# BabyDriver.net
KiCad netlist of a schematic drawn in EAGLE
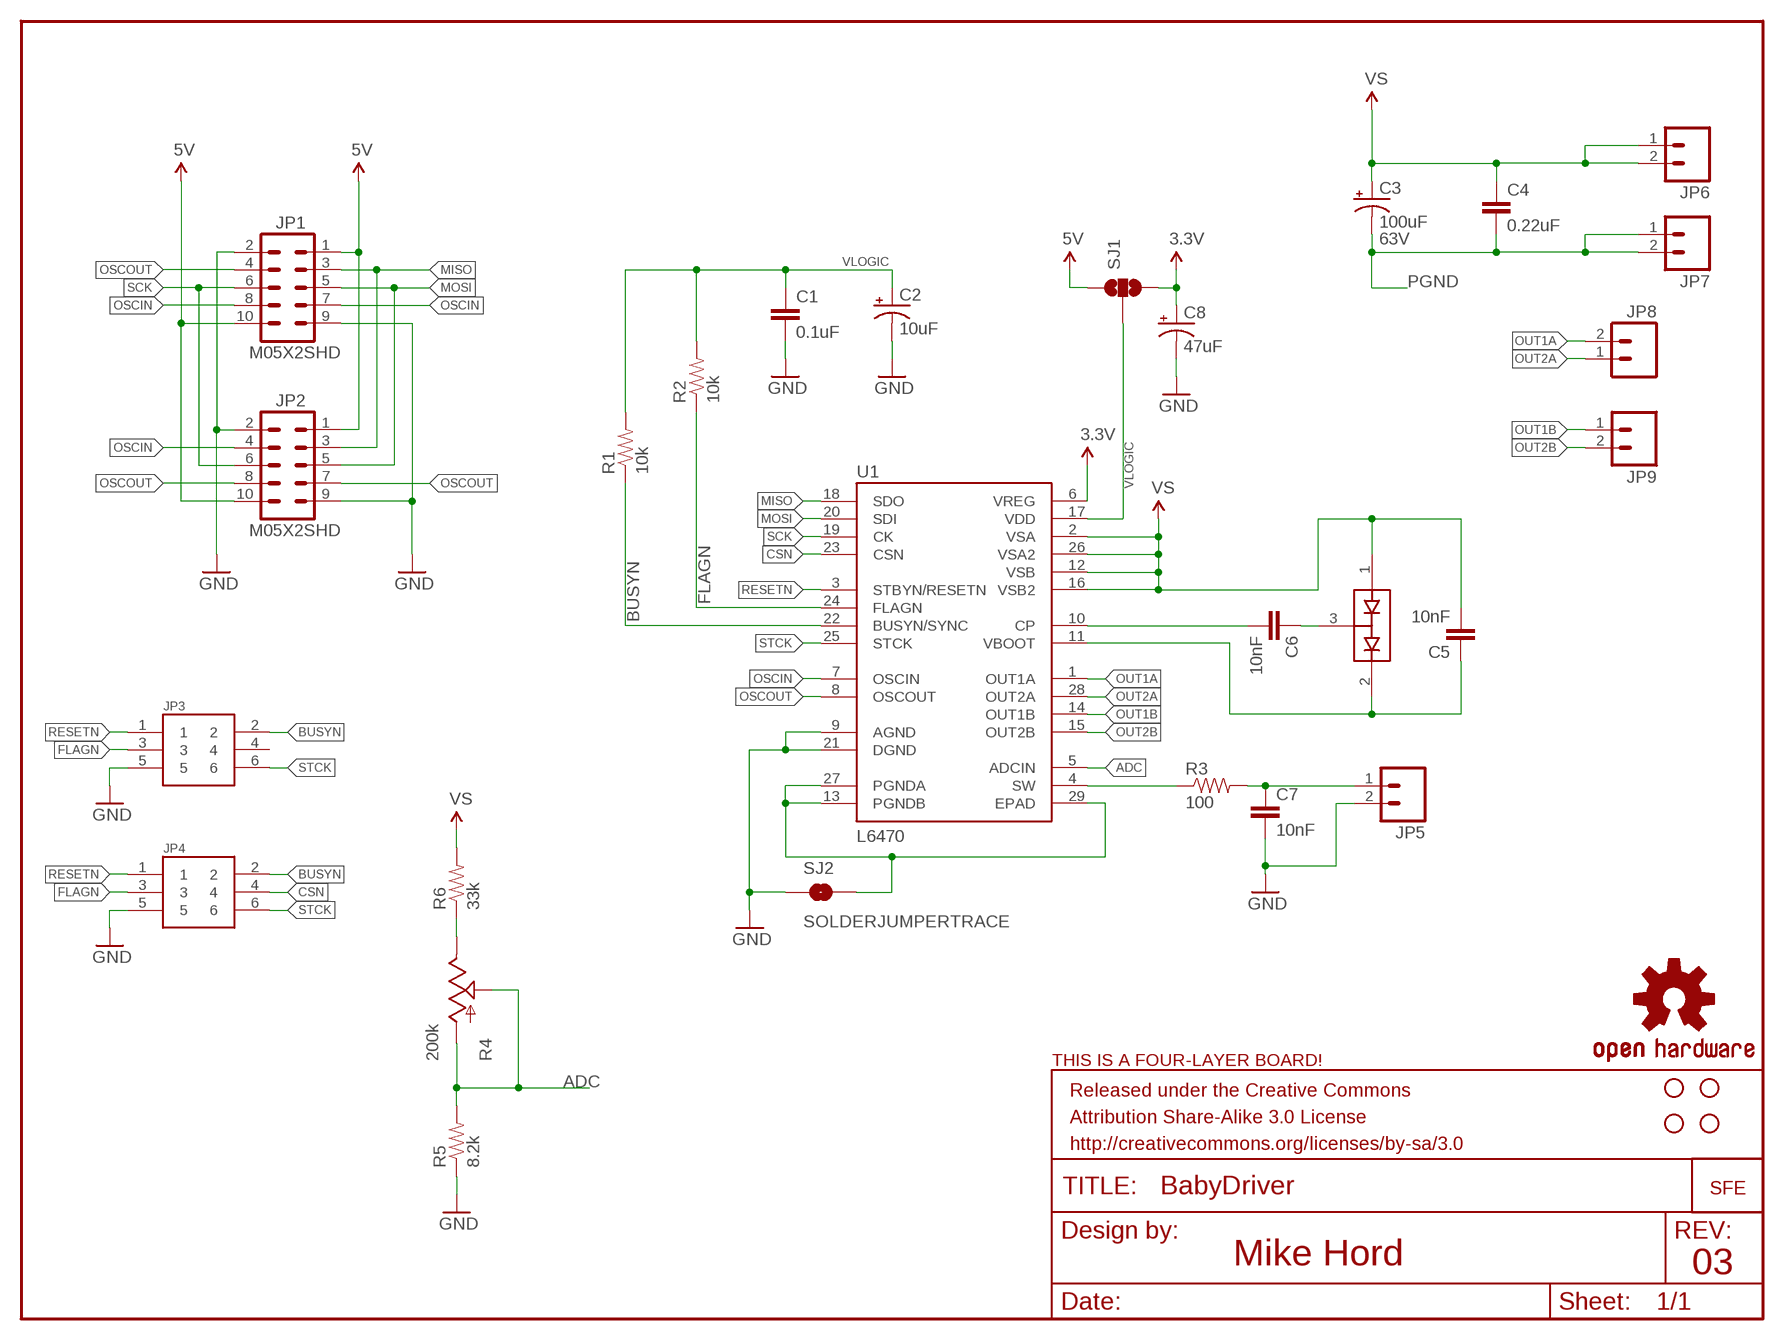
[diagram p0: schematic, sheet 1]

(export (version "E")
  (design (tool "Eeschema 10.0.6"))
  (components
    (comp (ref "C1")
      (value "0.1uF")
      (footprint "eagle-import:0402-CAP")
      (libsource (lib "eagle-import") (part ".1UF-CER"))
    )
    (comp (ref "C2")
      (value "10uF")
      (footprint "eagle-import:EIA3216")
      (libsource (lib "eagle-import") (part "10UF-TANT"))
    )
    (comp (ref "C3")
      (value "100uF")
      (footprint "eagle-import:PANASONIC_H13")
      (libsource (lib "eagle-import") (part "100UF-ELECT"))
    )
    (comp (ref "C4")
      (value "0.22uF")
      (footprint "eagle-import:0402-CAP")
      (libsource (lib "eagle-import") (part ".22UF-CER"))
    )
    (comp (ref "C5")
      (value "10nF")
      (footprint "eagle-import:0402-CAP")
      (libsource (lib "eagle-import") (part "10NF-CER"))
    )
    (comp (ref "C6")
      (value "10nF")
      (footprint "eagle-import:0402-CAP")
      (libsource (lib "eagle-import") (part "10NF-CER"))
    )
    (comp (ref "C7")
      (value "10nF")
      (footprint "eagle-import:0402-CAP")
      (libsource (lib "eagle-import") (part "10NF-CER"))
    )
    (comp (ref "C8")
      (value "47uF")
      (footprint "eagle-import:EIA3528")
      (libsource (lib "eagle-import") (part "47UF-TANT"))
    )
    (comp (ref "D1")
      (value "BAV99")
      (footprint "eagle-import:SOT23")
      (libsource (lib "eagle-import") (part "BAV99"))
    )
    (comp (ref "FRAME1")
      (value "FRAME-LETTER")
      (footprint "eagle-import:CREATIVE_COMMONS")
      (libsource (lib "eagle-import") (part "FRAME-LETTER"))
    )
    (comp (ref "JP1")
      (value "M05X2SHD")
      (footprint "eagle-import:2X5-SHROUDED")
      (libsource (lib "eagle-import") (part "M05X2SHD"))
    )
    (comp (ref "JP2")
      (value "M05X2SHD")
      (footprint "eagle-import:2X5-SHROUDED")
      (libsource (lib "eagle-import") (part "M05X2SHD"))
    )
    (comp (ref "JP3")
      (value "M03X2")
      (footprint "eagle-import:2X3-SHROUDED")
      (libsource (lib "eagle-import") (part "M03X2"))
    )
    (comp (ref "JP4")
      (value "M03X2")
      (footprint "eagle-import:2X3-SHROUDED")
      (libsource (lib "eagle-import") (part "M03X2"))
    )
    (comp (ref "JP5")
      (value "M023.5MM")
      (footprint "eagle-import:SCREWTERMINAL-3.5MM-2")
      (libsource (lib "eagle-import") (part "M023.5MM"))
    )
    (comp (ref "JP6")
      (value "M023.5MM")
      (footprint "eagle-import:SCREWTERMINAL-3.5MM-2")
      (libsource (lib "eagle-import") (part "M023.5MM"))
    )
    (comp (ref "JP7")
      (value "M023.5MM")
      (footprint "eagle-import:SCREWTERMINAL-3.5MM-2")
      (libsource (lib "eagle-import") (part "M023.5MM"))
    )
    (comp (ref "JP8")
      (value "M023.5MM")
      (footprint "eagle-import:SCREWTERMINAL-3.5MM-2")
      (libsource (lib "eagle-import") (part "M023.5MM"))
    )
    (comp (ref "JP9")
      (value "M023.5MM")
      (footprint "eagle-import:SCREWTERMINAL-3.5MM-2")
      (libsource (lib "eagle-import") (part "M023.5MM"))
    )
    (comp (ref "LOGO1")
      (value "OSHW-LOGOS")
      (footprint "eagle-import:OSHW-LOGO-S")
      (libsource (lib "eagle-import") (part "OSHW-LOGOS"))
    )
    (comp (ref "LOGO2")
      (value "LOGO-SFENEW")
      (footprint "eagle-import:SFE-NEW-WEBLOGO")
      (libsource (lib "eagle-import") (part "LOGO-SFENEW"))
    )
    (comp (ref "R1")
      (value "10k")
      (footprint "eagle-import:0402-RES")
      (libsource (lib "eagle-import") (part "10K-1%RES-00824"))
    )
    (comp (ref "R2")
      (value "10k")
      (footprint "eagle-import:0402-RES")
      (libsource (lib "eagle-import") (part "10K-1%RES-00824"))
    )
    (comp (ref "R3")
      (value "100")
      (footprint "eagle-import:0402-RES")
      (libsource (lib "eagle-import") (part "100-1%"))
    )
    (comp (ref "R4")
      (value "200k")
      (footprint "eagle-import:3362U")
      (libsource (lib "eagle-import") (part "POT100K_3362U"))
    )
    (comp (ref "R5")
      (value "8.2k")
      (footprint "eagle-import:0402-RES")
      (libsource (lib "eagle-import") (part "8.2K-5%"))
    )
    (comp (ref "R6")
      (value "33k")
      (footprint "eagle-import:0402-RES")
      (libsource (lib "eagle-import") (part "33K-1%"))
    )
    (comp (ref "SJ1")
      (value "SOLDERJUMPER_2WAYPASTE1&2")
      (footprint "eagle-import:SJ_3_PASTE1&2")
      (libsource (lib "eagle-import") (part "SOLDERJUMPER_2WAYPASTE1&2"))
    )
    (comp (ref "SJ2")
      (value "SOLDERJUMPERTRACE")
      (footprint "eagle-import:SJ_2S-TRACE")
      (libsource (lib "eagle-import") (part "SOLDERJUMPERTRACE"))
    )
    (comp (ref "STANDOFF1")
      (value "STAND-OFF")
      (footprint "eagle-import:STAND-OFF")
      (libsource (lib "eagle-import") (part "STAND-OFF"))
    )
    (comp (ref "STANDOFF2")
      (value "STAND-OFF")
      (footprint "eagle-import:STAND-OFF")
      (libsource (lib "eagle-import") (part "STAND-OFF"))
    )
    (comp (ref "STANDOFF3")
      (value "STAND-OFF")
      (footprint "eagle-import:STAND-OFF")
      (libsource (lib "eagle-import") (part "STAND-OFF"))
    )
    (comp (ref "STANDOFF4")
      (value "STAND-OFF")
      (footprint "eagle-import:STAND-OFF")
      (libsource (lib "eagle-import") (part "STAND-OFF"))
    )
    (comp (ref "U$4")
      (value "FOUR_LAYER_WARNING")
      (footprint "eagle-import:FOUR_LAYER_WARNING")
      (libsource (lib "eagle-import") (part "FOUR_LAYER_WARNING"))
    )
    (comp (ref "U1")
      (value "L6470")
      (footprint "eagle-import:HTSSOP28")
      (libsource (lib "eagle-import") (part "L6470"))
    )
  )
  (nets
    (net (code "1") (name "/PGND") (class "Default")
      (node (ref "C3") (pin "-") (pinfunction "-_-") (pintype "passive"))
      (node (ref "C4") (pin "2") (pinfunction "2_2") (pintype "passive"))
      (node (ref "JP7") (pin "1") (pinfunction "1_1") (pintype "passive"))
      (node (ref "JP7") (pin "2") (pinfunction "2_2") (pintype "passive"))
      (node (ref "SJ2") (pin "2") (pinfunction "2_2") (pintype "passive"))
      (node (ref "U1") (pin "13") (pinfunction "PGNDB_13") (pintype "bidirectional"))
      (node (ref "U1") (pin "27") (pinfunction "PGNDA_27") (pintype "bidirectional"))
      (node (ref "U1") (pin "29") (pinfunction "EPAD_29") (pintype "bidirectional"))
    )
    (net (code "2") (name "/VLOGIC") (class "Default")
      (node (ref "C1") (pin "1") (pinfunction "1_1") (pintype "passive"))
      (node (ref "C2") (pin "A") (pinfunction "+_A") (pintype "passive"))
      (node (ref "R1") (pin "2") (pinfunction "2_2") (pintype "passive"))
      (node (ref "R2") (pin "2") (pinfunction "2_2") (pintype "passive"))
      (node (ref "SJ1") (pin "2") (pinfunction "2_2") (pintype "passive"))
      (node (ref "U1") (pin "17") (pinfunction "VDD_17") (pintype "bidirectional"))
    )
    (net (code "3") (name "3.3V") (class "Default")
      (node (ref "C8") (pin "A") (pinfunction "+_A") (pintype "passive"))
      (node (ref "SJ1") (pin "3") (pinfunction "3_3") (pintype "passive"))
      (node (ref "U1") (pin "6") (pinfunction "VREG_6") (pintype "bidirectional"))
    )
    (net (code "4") (name "5V") (class "Default")
      (node (ref "JP1") (pin "1") (pinfunction "1_1") (pintype "passive"))
      (node (ref "JP1") (pin "10") (pinfunction "10_10") (pintype "passive"))
      (node (ref "JP2") (pin "1") (pinfunction "1_1") (pintype "passive"))
      (node (ref "JP2") (pin "10") (pinfunction "10_10") (pintype "passive"))
      (node (ref "SJ1") (pin "1") (pinfunction "1_1") (pintype "passive"))
    )
    (net (code "5") (name "ADC") (class "Default")
      (node (ref "R4") (pin "P$2") (pinfunction "S_P$2") (pintype "passive"))
      (node (ref "R4") (pin "P$3") (pinfunction "A_P$3") (pintype "passive"))
      (node (ref "R5") (pin "2") (pinfunction "2_2") (pintype "passive"))
      (node (ref "U1") (pin "5") (pinfunction "ADCIN_5") (pintype "bidirectional"))
    )
    (net (code "6") (name "BUSYN") (class "Default")
      (node (ref "JP3") (pin "2") (pinfunction "2_2") (pintype "bidirectional"))
      (node (ref "JP4") (pin "2") (pinfunction "2_2") (pintype "bidirectional"))
      (node (ref "R1") (pin "1") (pinfunction "1_1") (pintype "passive"))
      (node (ref "U1") (pin "22") (pinfunction "BUSYN/SYNC_22") (pintype "bidirectional"))
    )
    (net (code "7") (name "CSN") (class "Default")
      (node (ref "JP4") (pin "4") (pinfunction "4_4") (pintype "bidirectional"))
      (node (ref "U1") (pin "23") (pinfunction "CSN_23") (pintype "bidirectional"))
    )
    (net (code "8") (name "FLAGN") (class "Default")
      (node (ref "JP3") (pin "3") (pinfunction "3_3") (pintype "bidirectional"))
      (node (ref "JP4") (pin "3") (pinfunction "3_3") (pintype "bidirectional"))
      (node (ref "R2") (pin "1") (pinfunction "1_1") (pintype "passive"))
      (node (ref "U1") (pin "24") (pinfunction "FLAGN_24") (pintype "bidirectional"))
    )
    (net (code "9") (name "GND") (class "Default")
      (node (ref "C1") (pin "2") (pinfunction "2_2") (pintype "passive"))
      (node (ref "C2") (pin "C") (pinfunction "-_C") (pintype "passive"))
      (node (ref "C7") (pin "2") (pinfunction "2_2") (pintype "passive"))
      (node (ref "C8") (pin "C") (pinfunction "-_C") (pintype "passive"))
      (node (ref "JP1") (pin "2") (pinfunction "2_2") (pintype "passive"))
      (node (ref "JP1") (pin "9") (pinfunction "9_9") (pintype "passive"))
      (node (ref "JP2") (pin "2") (pinfunction "2_2") (pintype "passive"))
      (node (ref "JP2") (pin "9") (pinfunction "9_9") (pintype "passive"))
      (node (ref "JP3") (pin "5") (pinfunction "5_5") (pintype "bidirectional"))
      (node (ref "JP4") (pin "5") (pinfunction "5_5") (pintype "bidirectional"))
      (node (ref "JP5") (pin "2") (pinfunction "2_2") (pintype "passive"))
      (node (ref "R5") (pin "1") (pinfunction "1_1") (pintype "passive"))
      (node (ref "SJ2") (pin "1") (pinfunction "1_1") (pintype "passive"))
      (node (ref "U1") (pin "21") (pinfunction "DGND_21") (pintype "bidirectional"))
      (node (ref "U1") (pin "9") (pinfunction "AGND_9") (pintype "bidirectional"))
    )
    (net (code "10") (name "MISO") (class "Default")
      (node (ref "JP1") (pin "3") (pinfunction "3_3") (pintype "passive"))
      (node (ref "JP2") (pin "3") (pinfunction "3_3") (pintype "passive"))
      (node (ref "U1") (pin "18") (pinfunction "SDO_18") (pintype "bidirectional"))
    )
    (net (code "11") (name "MOSI") (class "Default")
      (node (ref "JP1") (pin "5") (pinfunction "5_5") (pintype "passive"))
      (node (ref "JP2") (pin "5") (pinfunction "5_5") (pintype "passive"))
      (node (ref "U1") (pin "20") (pinfunction "SDI_20") (pintype "bidirectional"))
    )
    (net (code "12") (name "Net-(C7-Pad1)") (class "Default")
      (node (ref "C7") (pin "1") (pinfunction "1_1") (pintype "passive"))
      (node (ref "JP5") (pin "1") (pinfunction "1_1") (pintype "passive"))
      (node (ref "R3") (pin "2") (pinfunction "2_2") (pintype "passive"))
    )
    (net (code "13") (name "Net-(D1-C2)") (class "Default")
      (node (ref "C5") (pin "1") (pinfunction "1_1") (pintype "passive"))
      (node (ref "D1") (pin "2") (pinfunction "C2_2") (pintype "bidirectional"))
      (node (ref "U1") (pin "11") (pinfunction "VBOOT_11") (pintype "bidirectional"))
    )
    (net (code "14") (name "Net-(D1-COM)") (class "Default")
      (node (ref "C6") (pin "1") (pinfunction "1_1") (pintype "passive"))
      (node (ref "D1") (pin "3") (pinfunction "COM_3") (pintype "bidirectional"))
    )
    (net (code "15") (name "Net-(R4-E)") (class "Default")
      (node (ref "R4") (pin "P$1") (pinfunction "E_P$1") (pintype "passive"))
      (node (ref "R6") (pin "1") (pinfunction "1_1") (pintype "passive"))
    )
    (net (code "16") (name "Net-(U1-CP)") (class "Default")
      (node (ref "C6") (pin "2") (pinfunction "2_2") (pintype "passive"))
      (node (ref "U1") (pin "10") (pinfunction "CP_10") (pintype "bidirectional"))
    )
    (net (code "17") (name "Net-(U1-SW)") (class "Default")
      (node (ref "R3") (pin "1") (pinfunction "1_1") (pintype "passive"))
      (node (ref "U1") (pin "4") (pinfunction "SW_4") (pintype "bidirectional"))
    )
    (net (code "18") (name "OSCIN") (class "Default")
      (node (ref "JP1") (pin "7") (pinfunction "7_7") (pintype "passive"))
      (node (ref "JP1") (pin "8") (pinfunction "8_8") (pintype "passive"))
      (node (ref "JP2") (pin "4") (pinfunction "4_4") (pintype "passive"))
      (node (ref "U1") (pin "7") (pinfunction "OSCIN_7") (pintype "bidirectional"))
    )
    (net (code "19") (name "OSCOUT") (class "Default")
      (node (ref "JP1") (pin "4") (pinfunction "4_4") (pintype "passive"))
      (node (ref "JP2") (pin "7") (pinfunction "7_7") (pintype "passive"))
      (node (ref "JP2") (pin "8") (pinfunction "8_8") (pintype "passive"))
      (node (ref "U1") (pin "8") (pinfunction "OSCOUT_8") (pintype "bidirectional"))
    )
    (net (code "20") (name "OUT1A") (class "Default")
      (node (ref "JP8") (pin "2") (pinfunction "2_2") (pintype "passive"))
      (node (ref "U1") (pin "1") (pinfunction "OUT1A_1") (pintype "bidirectional"))
    )
    (net (code "21") (name "OUT1B") (class "Default")
      (node (ref "JP9") (pin "1") (pinfunction "1_1") (pintype "passive"))
      (node (ref "U1") (pin "14") (pinfunction "OUT1B_14") (pintype "bidirectional"))
    )
    (net (code "22") (name "OUT2A") (class "Default")
      (node (ref "JP8") (pin "1") (pinfunction "1_1") (pintype "passive"))
      (node (ref "U1") (pin "28") (pinfunction "OUT2A_28") (pintype "bidirectional"))
    )
    (net (code "23") (name "OUT2B") (class "Default")
      (node (ref "JP9") (pin "2") (pinfunction "2_2") (pintype "passive"))
      (node (ref "U1") (pin "15") (pinfunction "OUT2B_15") (pintype "bidirectional"))
    )
    (net (code "24") (name "RESETN") (class "Default")
      (node (ref "JP3") (pin "1") (pinfunction "1_1") (pintype "bidirectional"))
      (node (ref "JP4") (pin "1") (pinfunction "1_1") (pintype "bidirectional"))
      (node (ref "U1") (pin "3") (pinfunction "STBYN/RESETN_3") (pintype "bidirectional"))
    )
    (net (code "25") (name "SCK") (class "Default")
      (node (ref "JP1") (pin "6") (pinfunction "6_6") (pintype "passive"))
      (node (ref "JP2") (pin "6") (pinfunction "6_6") (pintype "passive"))
      (node (ref "U1") (pin "19") (pinfunction "CK_19") (pintype "bidirectional"))
    )
    (net (code "26") (name "STCK") (class "Default")
      (node (ref "JP3") (pin "6") (pinfunction "6_6") (pintype "bidirectional"))
      (node (ref "JP4") (pin "6") (pinfunction "6_6") (pintype "bidirectional"))
      (node (ref "U1") (pin "25") (pinfunction "STCK_25") (pintype "bidirectional"))
    )
    (net (code "27") (name "VS") (class "Default")
      (node (ref "C3") (pin "+") (pinfunction "+_+") (pintype "passive"))
      (node (ref "C4") (pin "1") (pinfunction "1_1") (pintype "passive"))
      (node (ref "C5") (pin "2") (pinfunction "2_2") (pintype "passive"))
      (node (ref "D1") (pin "1") (pinfunction "A1_1") (pintype "bidirectional"))
      (node (ref "JP6") (pin "1") (pinfunction "1_1") (pintype "passive"))
      (node (ref "JP6") (pin "2") (pinfunction "2_2") (pintype "passive"))
      (node (ref "R6") (pin "2") (pinfunction "2_2") (pintype "passive"))
      (node (ref "U1") (pin "12") (pinfunction "VSB_12") (pintype "bidirectional"))
      (node (ref "U1") (pin "16") (pinfunction "VSB2_16") (pintype "bidirectional"))
      (node (ref "U1") (pin "2") (pinfunction "VSA_2") (pintype "bidirectional"))
      (node (ref "U1") (pin "26") (pinfunction "VSA2_26") (pintype "bidirectional"))
    )
    (net (code "28") (name "unconnected-(JP3-Pad4)") (class "Default")
      (node (ref "JP3") (pin "4") (pinfunction "4_4") (pintype "bidirectional"))
    )
  )
)
